# sheet_top.net
KiCad netlist of a schematic drawn in Altium Designer
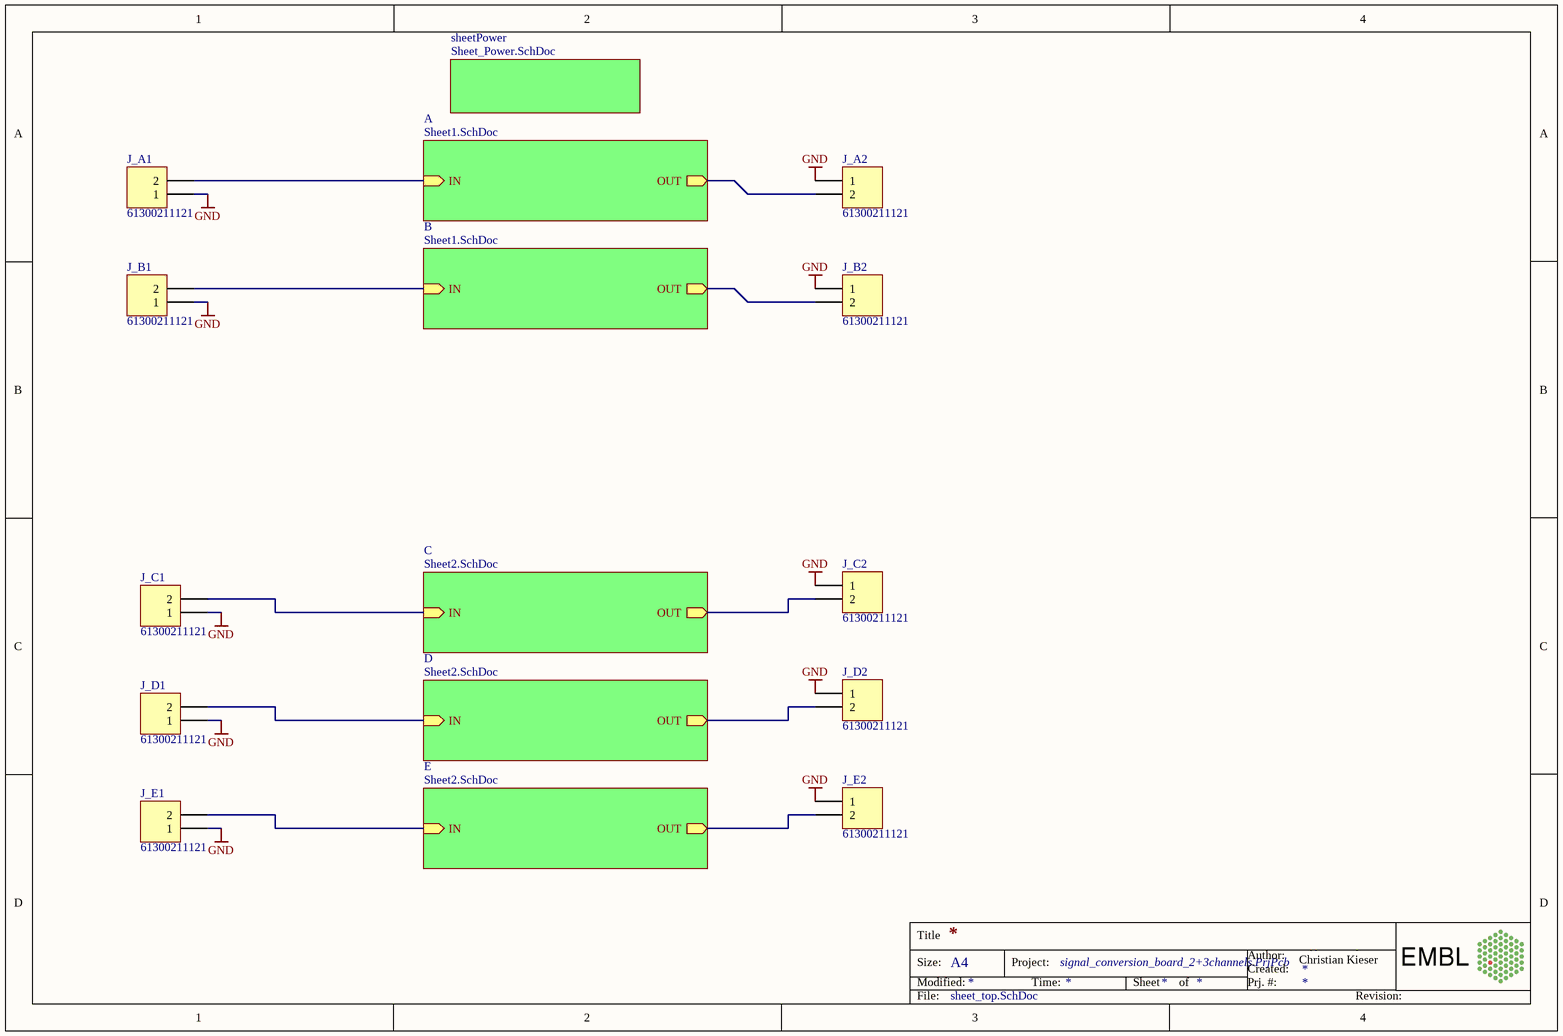
[diagram p0: sheet_top.SchDoc]

(export (version "E")
  (design (tool "Eeschema 10.0.6"))
  (components
    (comp (ref "J_A1")
      (value "61300211121")
      (footprint "61300211121")
      (description "2Pol; gerade; WR-PHD 2.54 mm THT Pin Header")
      (fields (field (name "MANUFACTURER") "Wurth Electronics"))
      (libsource (lib "") (part "CMP-001-0071-1_1"))
    )
    (comp (ref "J_A2")
      (value "61300211121")
      (footprint "61300211121")
      (description "2Pol; gerade; WR-PHD 2.54 mm THT Pin Header")
      (fields (field (name "MANUFACTURER") "Wurth Electronics"))
      (libsource (lib "Altium Vault EMBL 3") (part "61300211121"))
    )
    (comp (ref "J_B1")
      (value "61300211121")
      (footprint "61300211121")
      (description "2Pol; gerade; WR-PHD 2.54 mm THT Pin Header")
      (fields (field (name "MANUFACTURER") "Wurth Electronics"))
      (libsource (lib "") (part "CMP-001-0071-1_1"))
    )
    (comp (ref "J_B2")
      (value "61300211121")
      (footprint "61300211121")
      (description "2Pol; gerade; WR-PHD 2.54 mm THT Pin Header")
      (fields (field (name "MANUFACTURER") "Wurth Electronics"))
      (libsource (lib "Altium Vault EMBL 3") (part "CMP-001-0071-1"))
    )
    (comp (ref "J_C1")
      (value "61300211121")
      (footprint "61300211121")
      (description "2Pol; gerade; WR-PHD 2.54 mm THT Pin Header")
      (fields (field (name "MANUFACTURER") "Wurth Electronics"))
      (libsource (lib "") (part "CMP-001-0071-1_1"))
    )
    (comp (ref "J_C2")
      (value "61300211121")
      (footprint "61300211121")
      (description "2Pol; gerade; WR-PHD 2.54 mm THT Pin Header")
      (fields (field (name "MANUFACTURER") "Wurth Electronics"))
      (libsource (lib "Altium Vault EMBL 3") (part "CMP-001-0071-1"))
    )
    (comp (ref "J_D1")
      (value "61300211121")
      (footprint "61300211121")
      (description "2Pol; gerade; WR-PHD 2.54 mm THT Pin Header")
      (fields (field (name "MANUFACTURER") "Wurth Electronics"))
      (libsource (lib "") (part "CMP-001-0071-1_1"))
    )
    (comp (ref "J_D2")
      (value "61300211121")
      (footprint "61300211121")
      (description "2Pol; gerade; WR-PHD 2.54 mm THT Pin Header")
      (fields (field (name "MANUFACTURER") "Wurth Electronics"))
      (libsource (lib "Altium Vault EMBL 3") (part "CMP-001-0071-1"))
    )
    (comp (ref "J_E1")
      (value "61300211121")
      (footprint "61300211121")
      (description "2Pol; gerade; WR-PHD 2.54 mm THT Pin Header")
      (fields (field (name "MANUFACTURER") "Wurth Electronics"))
      (libsource (lib "") (part "CMP-001-0071-1_1"))
    )
    (comp (ref "J_E2")
      (value "61300211121")
      (footprint "61300211121")
      (description "2Pol; gerade; WR-PHD 2.54 mm THT Pin Header")
      (fields (field (name "MANUFACTURER") "Wurth Electronics"))
      (libsource (lib "Altium Vault EMBL 3") (part "CMP-001-0071-1"))
    )
  )
  (nets
    (net (code "1") (name "/IN") (class "Default")
      (node (ref "J_A1") (pin "2") (pinfunction "2_2") (pintype "passive"))
    )
    (net (code "2") (name "/IN_1") (class "Default")
      (node (ref "J_B1") (pin "2") (pinfunction "2_2") (pintype "passive"))
    )
    (net (code "3") (name "/IN_2") (class "Default")
      (node (ref "J_C1") (pin "2") (pinfunction "2_2") (pintype "passive"))
    )
    (net (code "4") (name "/IN_3") (class "Default")
      (node (ref "J_E1") (pin "2") (pinfunction "2_2") (pintype "passive"))
    )
    (net (code "5") (name "/IN_4") (class "Default")
      (node (ref "J_D1") (pin "2") (pinfunction "2_2") (pintype "passive"))
    )
    (net (code "6") (name "/OUT") (class "Default")
      (node (ref "J_C2") (pin "2") (pinfunction "2_2") (pintype "passive"))
    )
    (net (code "7") (name "/OUT_1") (class "Default")
      (node (ref "J_E2") (pin "2") (pinfunction "2_2") (pintype "passive"))
    )
    (net (code "8") (name "/OUT_2") (class "Default")
      (node (ref "J_D2") (pin "2") (pinfunction "2_2") (pintype "passive"))
    )
    (net (code "9") (name "/OUT_3") (class "Default")
      (node (ref "J_B2") (pin "2") (pinfunction "2_2") (pintype "passive"))
    )
    (net (code "10") (name "/OUT_4") (class "Default")
      (node (ref "J_A2") (pin "2") (pinfunction "2_2") (pintype "passive"))
    )
    (net (code "11") (name "GND") (class "Default")
      (node (ref "J_A1") (pin "1") (pinfunction "1_1") (pintype "passive"))
      (node (ref "J_A2") (pin "1") (pinfunction "1_1") (pintype "passive"))
      (node (ref "J_B1") (pin "1") (pinfunction "1_1") (pintype "passive"))
      (node (ref "J_B2") (pin "1") (pinfunction "1_1") (pintype "passive"))
      (node (ref "J_C1") (pin "1") (pinfunction "1_1") (pintype "passive"))
      (node (ref "J_C2") (pin "1") (pinfunction "1_1") (pintype "passive"))
      (node (ref "J_D1") (pin "1") (pinfunction "1_1") (pintype "passive"))
      (node (ref "J_D2") (pin "1") (pinfunction "1_1") (pintype "passive"))
      (node (ref "J_E1") (pin "1") (pinfunction "1_1") (pintype "passive"))
      (node (ref "J_E2") (pin "1") (pinfunction "1_1") (pintype "passive"))
    )
  )
)
